# VizeSinavi.net
KiCad netlist of a schematic drawn in EAGLE
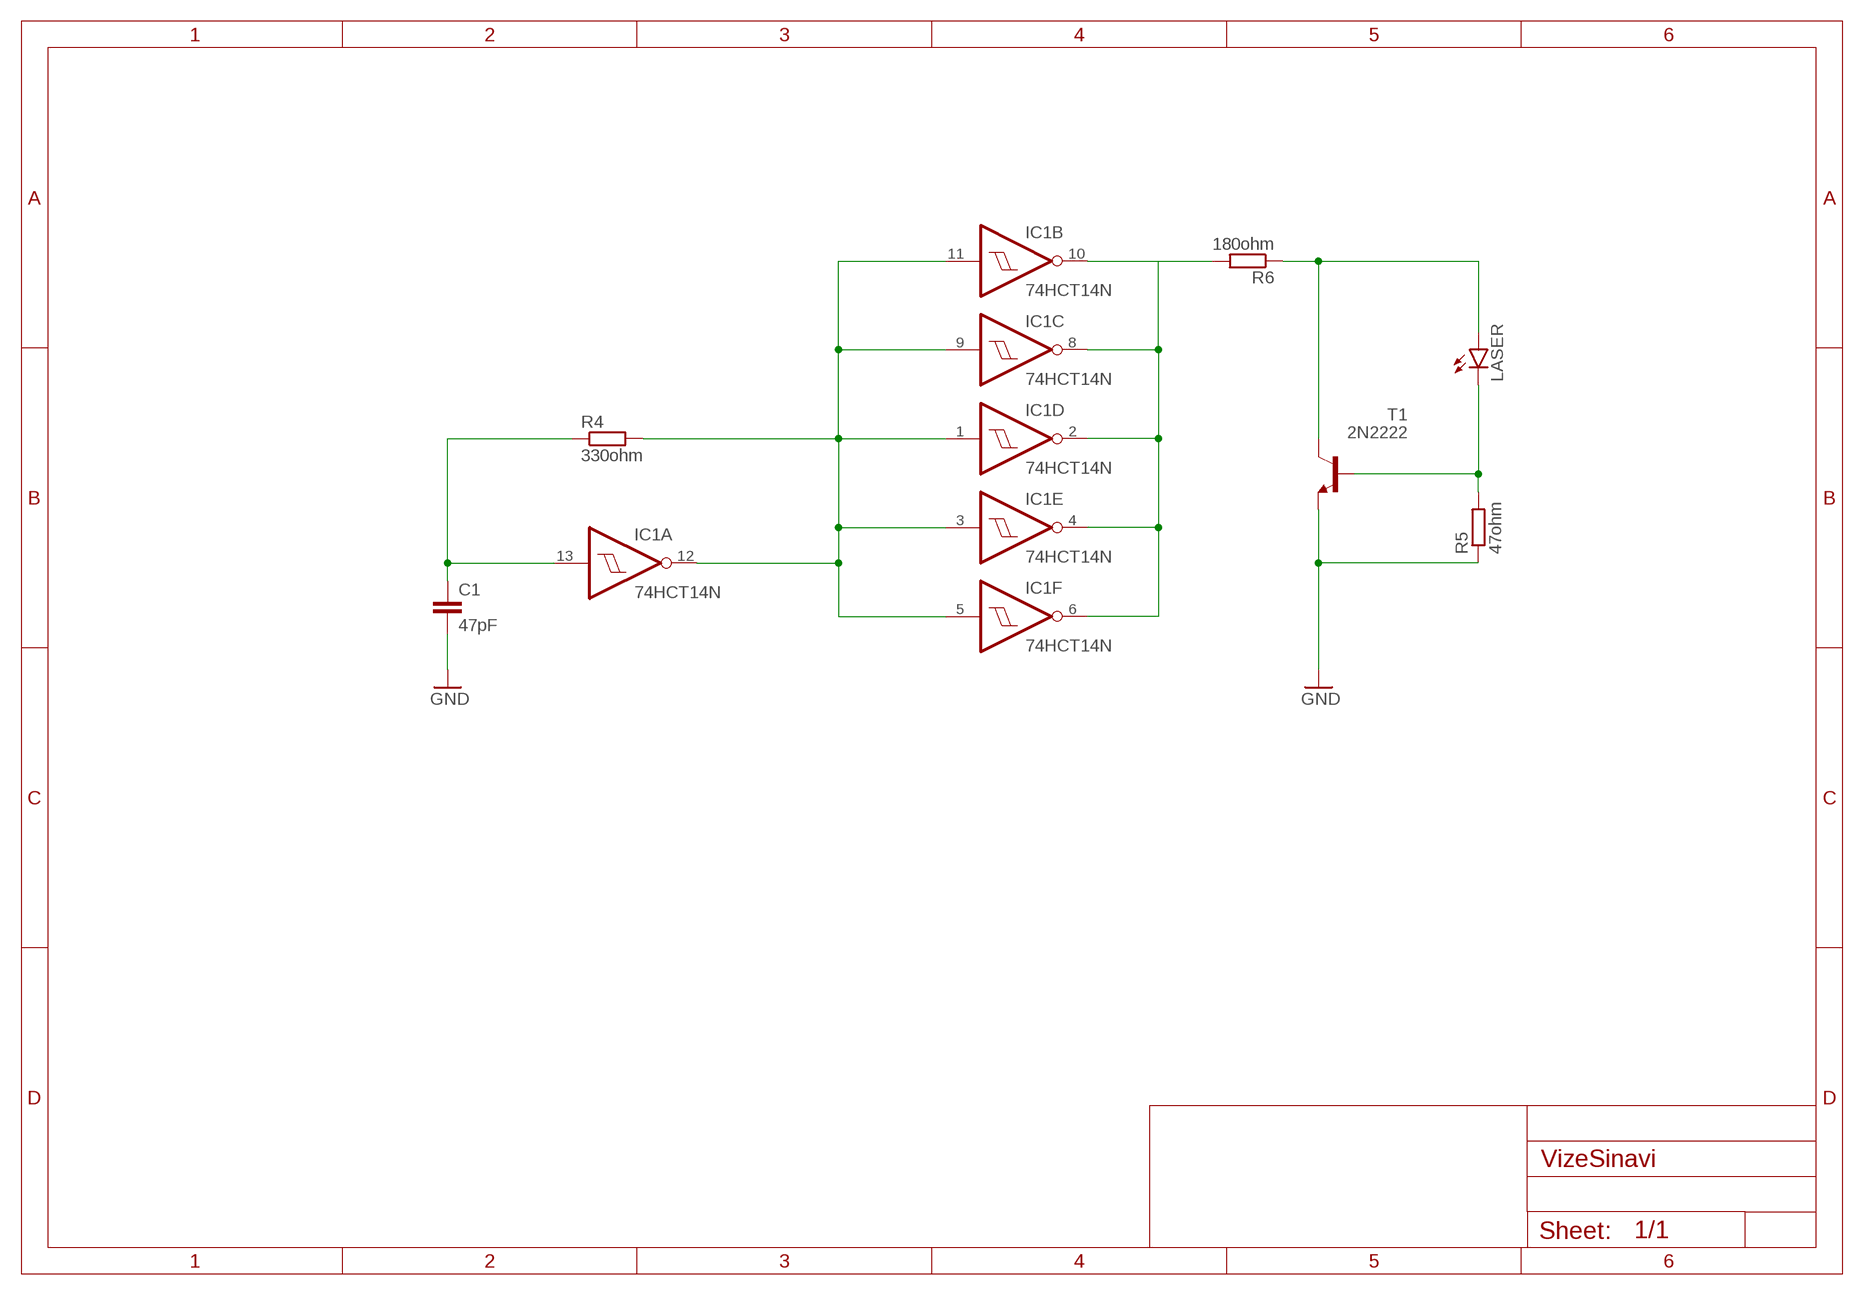
[diagram p0: schematic, sheet 1]

(export (version "E")
  (design (tool "Eeschema 10.0.6"))
  (components
    (comp (ref "C1")
      (value "47pF")
      (footprint "eagle-import:C2.5-3")
      (libsource (lib "eagle-import") (part "C2,5-3"))
    )
    (comp (ref "IC1")
      (value "74HCT14N")
      (footprint "eagle-import:DIL14")
      (libsource (lib "eagle-import") (part "7414NHCT"))
    )
    (comp (ref "LASER")
      (value "LED5MM")
      (footprint "eagle-import:LED5MM")
      (libsource (lib "eagle-import") (part "LED5MM"))
    )
    (comp (ref "R4")
      (value "330ohm")
      (footprint "eagle-import:0204_5")
      (libsource (lib "eagle-import") (part "R-EU_0204/5"))
    )
    (comp (ref "R5")
      (value "47ohm")
      (footprint "eagle-import:0204_5")
      (libsource (lib "eagle-import") (part "R-EU_0204/5"))
    )
    (comp (ref "R6")
      (value "180ohm")
      (footprint "eagle-import:0204_5")
      (libsource (lib "eagle-import") (part "R-EU_0204/5"))
    )
    (comp (ref "T1")
      (value "2N2222")
      (footprint "eagle-import:TO18")
      (libsource (lib "eagle-import") (part "2N2222"))
    )
  )
  (nets
    (net (code "1") (name "GND") (class "Default")
      (node (ref "C1") (pin "2") (pinfunction "2_2") (pintype "passive"))
      (node (ref "R5") (pin "1") (pinfunction "1_1") (pintype "passive"))
      (node (ref "T1") (pin "1") (pinfunction "E_1") (pintype "passive"))
    )
    (net (code "2") (name "Net-(IC1A-I)") (class "Default")
      (node (ref "C1") (pin "1") (pinfunction "1_1") (pintype "passive"))
      (node (ref "IC1") (pin "13") (pinfunction "I_13") (pintype "input"))
      (node (ref "R4") (pin "1") (pinfunction "1_1") (pintype "passive"))
    )
    (net (code "3") (name "Net-(IC1A-O)") (class "Default")
      (node (ref "IC1") (pin "1") (pinfunction "I_1") (pintype "input"))
      (node (ref "IC1") (pin "11") (pinfunction "I_11") (pintype "input"))
      (node (ref "IC1") (pin "12") (pinfunction "O_12") (pintype "output"))
      (node (ref "IC1") (pin "3") (pinfunction "I_3") (pintype "input"))
      (node (ref "IC1") (pin "5") (pinfunction "I_5") (pintype "input"))
      (node (ref "IC1") (pin "9") (pinfunction "I_9") (pintype "input"))
      (node (ref "R4") (pin "2") (pinfunction "2_2") (pintype "passive"))
    )
    (net (code "4") (name "Net-(IC1B-O)") (class "Default")
      (node (ref "IC1") (pin "10") (pinfunction "O_10") (pintype "output"))
      (node (ref "R6") (pin "2") (pinfunction "2_2") (pintype "passive"))
    )
    (net (code "5") (name "Net-(IC1C-O)") (class "Default")
      (node (ref "IC1") (pin "2") (pinfunction "O_2") (pintype "output"))
      (node (ref "IC1") (pin "4") (pinfunction "O_4") (pintype "output"))
      (node (ref "IC1") (pin "6") (pinfunction "O_6") (pintype "output"))
      (node (ref "IC1") (pin "8") (pinfunction "O_8") (pintype "output"))
    )
    (net (code "6") (name "Net-(LASER-C)") (class "Default")
      (node (ref "LASER") (pin "K") (pinfunction "C_K") (pintype "passive"))
      (node (ref "R5") (pin "2") (pinfunction "2_2") (pintype "passive"))
      (node (ref "T1") (pin "2") (pinfunction "B_2") (pintype "passive"))
    )
    (net (code "7") (name "Net-(T1-C)") (class "Default")
      (node (ref "LASER") (pin "A") (pinfunction "A_A") (pintype "passive"))
      (node (ref "R6") (pin "1") (pinfunction "1_1") (pintype "passive"))
      (node (ref "T1") (pin "3") (pinfunction "C_3") (pintype "passive"))
    )
  )
)
